# TopSheet.net
KiCad netlist of a schematic drawn in Altium Designer
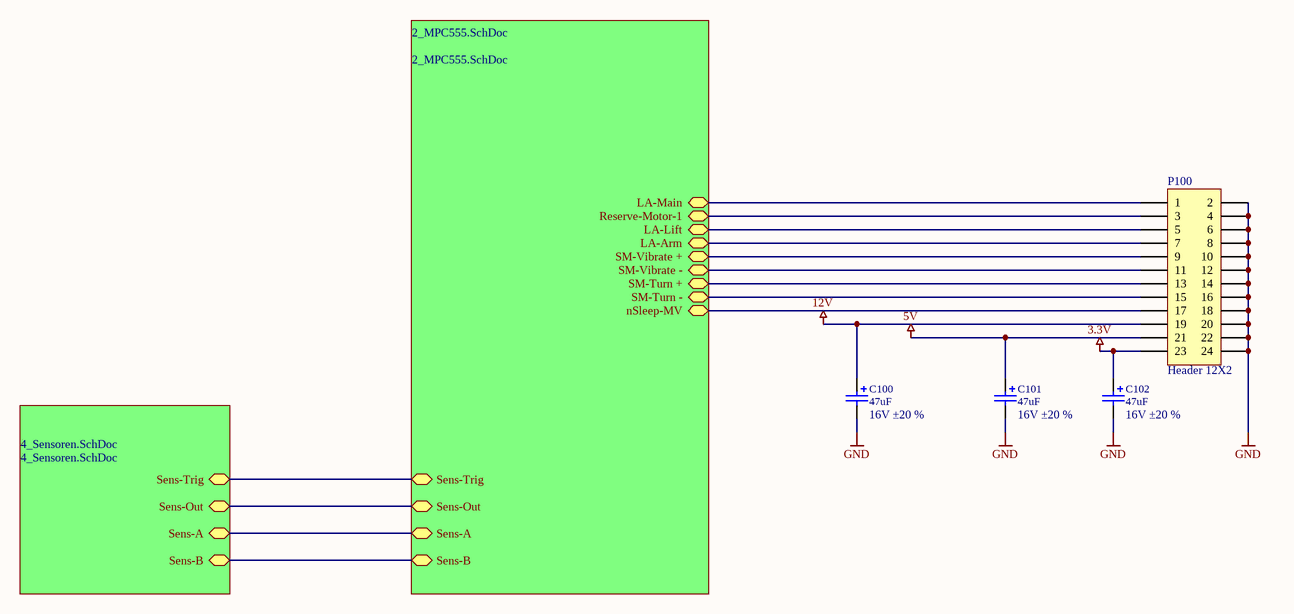
[diagram p0: TopSheet.schdoc]

(export (version "E")
  (design (tool "Eeschema 10.0.6"))
  (components
    (comp (ref "C100")
      (value "47uF")
      (footprint "CDE_CAP AVE CODE D_H")
      (description "ELKO, 47uF, 16V, CDE_AVE476M16D16T-F_AVE CODE D")
      (fields
        (field (name "MANUFACTURER") "Cornell Dubilier")
        (field (name "VALUEADDON") "16V ±20 %")
        (field (name "Comment") "AVE476M16D16T-F")
        (field (name "PUBLISHER") "Stefan Ursella, M.Eng")
      )
      (libsource (lib "IR-Sensor") (part "ELKO 47uF 16V"))
    )
    (comp (ref "C101")
      (value "47uF")
      (footprint "CDE_CAP AVE CODE D_H")
      (description "ELKO, 47uF, 16V, CDE_AVE476M16D16T-F_AVE CODE D")
      (fields
        (field (name "MANUFACTURER") "Cornell Dubilier")
        (field (name "VALUEADDON") "16V ±20 %")
        (field (name "Comment") "AVE476M16D16T-F")
        (field (name "PUBLISHER") "Stefan Ursella, M.Eng")
      )
      (libsource (lib "IR-Sensor") (part "ELKO 47uF 16V"))
    )
    (comp (ref "C102")
      (value "47uF")
      (footprint "CDE_CAP AVE CODE D_H")
      (description "ELKO, 47uF, 16V, CDE_AVE476M16D16T-F_AVE CODE D")
      (fields
        (field (name "MANUFACTURER") "Cornell Dubilier")
        (field (name "VALUEADDON") "16V ±20 %")
        (field (name "Comment") "AVE476M16D16T-F")
        (field (name "PUBLISHER") "Stefan Ursella, M.Eng")
      )
      (libsource (lib "IR-Sensor") (part "ELKO 47uF 16V"))
    )
    (comp (ref "P100")
      (value "Header 12X2")
      (footprint "HDR2X12")
      (description "Header, 12-Pin, Dual row")
      (fields (field (name "PUBLISHER") "Altium Limited"))
      (libsource (lib "Miscellaneous Connectors") (part "Header 12X2"))
    )
  )
  (nets
    (net (code "1") (name "/LA-Arm") (class "Default")
      (node (ref "P100") (pin "7") (pinfunction "7_7") (pintype "passive"))
    )
    (net (code "2") (name "/LA-Lift") (class "Default")
      (node (ref "P100") (pin "5") (pinfunction "5_5") (pintype "passive"))
    )
    (net (code "3") (name "/LA-Main") (class "Default")
      (node (ref "P100") (pin "1") (pinfunction "1_1") (pintype "passive"))
    )
    (net (code "4") (name "/Reserve-Motor-1") (class "Default")
      (node (ref "P100") (pin "3") (pinfunction "3_3") (pintype "passive"))
    )
    (net (code "5") (name "/SM-Turn +") (class "Default")
      (node (ref "P100") (pin "13") (pinfunction "13_13") (pintype "passive"))
    )
    (net (code "6") (name "/SM-Turn -") (class "Default")
      (node (ref "P100") (pin "15") (pinfunction "15_15") (pintype "passive"))
    )
    (net (code "7") (name "/SM-Vibrate +") (class "Default")
      (node (ref "P100") (pin "9") (pinfunction "9_9") (pintype "passive"))
    )
    (net (code "8") (name "/SM-Vibrate -") (class "Default")
      (node (ref "P100") (pin "11") (pinfunction "11_11") (pintype "passive"))
    )
    (net (code "13") (name "/nSleep-MV") (class "Default")
      (node (ref "P100") (pin "17") (pinfunction "17_17") (pintype "passive"))
    )
    (net (code "14") (name "3.3V") (class "Default")
      (node (ref "C102") (pin "1") (pinfunction "Pos_1") (pintype "passive"))
      (node (ref "P100") (pin "23") (pinfunction "23_23") (pintype "passive"))
    )
    (net (code "15") (name "5V") (class "Default")
      (node (ref "C101") (pin "1") (pinfunction "Pos_1") (pintype "passive"))
      (node (ref "P100") (pin "21") (pinfunction "21_21") (pintype "passive"))
    )
    (net (code "16") (name "12V") (class "Default")
      (node (ref "C100") (pin "1") (pinfunction "Pos_1") (pintype "passive"))
      (node (ref "P100") (pin "19") (pinfunction "19_19") (pintype "passive"))
    )
    (net (code "17") (name "GND") (class "Default")
      (node (ref "C100") (pin "2") (pinfunction "Neg_2") (pintype "passive"))
      (node (ref "C101") (pin "2") (pinfunction "Neg_2") (pintype "passive"))
      (node (ref "C102") (pin "2") (pinfunction "Neg_2") (pintype "passive"))
      (node (ref "P100") (pin "10") (pinfunction "10_10") (pintype "passive"))
      (node (ref "P100") (pin "12") (pinfunction "12_12") (pintype "passive"))
      (node (ref "P100") (pin "14") (pinfunction "14_14") (pintype "passive"))
      (node (ref "P100") (pin "16") (pinfunction "16_16") (pintype "passive"))
      (node (ref "P100") (pin "18") (pinfunction "18_18") (pintype "passive"))
      (node (ref "P100") (pin "2") (pinfunction "2_2") (pintype "passive"))
      (node (ref "P100") (pin "20") (pinfunction "20_20") (pintype "passive"))
      (node (ref "P100") (pin "22") (pinfunction "22_22") (pintype "passive"))
      (node (ref "P100") (pin "24") (pinfunction "24_24") (pintype "passive"))
      (node (ref "P100") (pin "4") (pinfunction "4_4") (pintype "passive"))
      (node (ref "P100") (pin "6") (pinfunction "6_6") (pintype "passive"))
      (node (ref "P100") (pin "8") (pinfunction "8_8") (pintype "passive"))
    )
  )
)
